# 01_MCU.net
KiCad netlist of a schematic drawn in Altium Designer
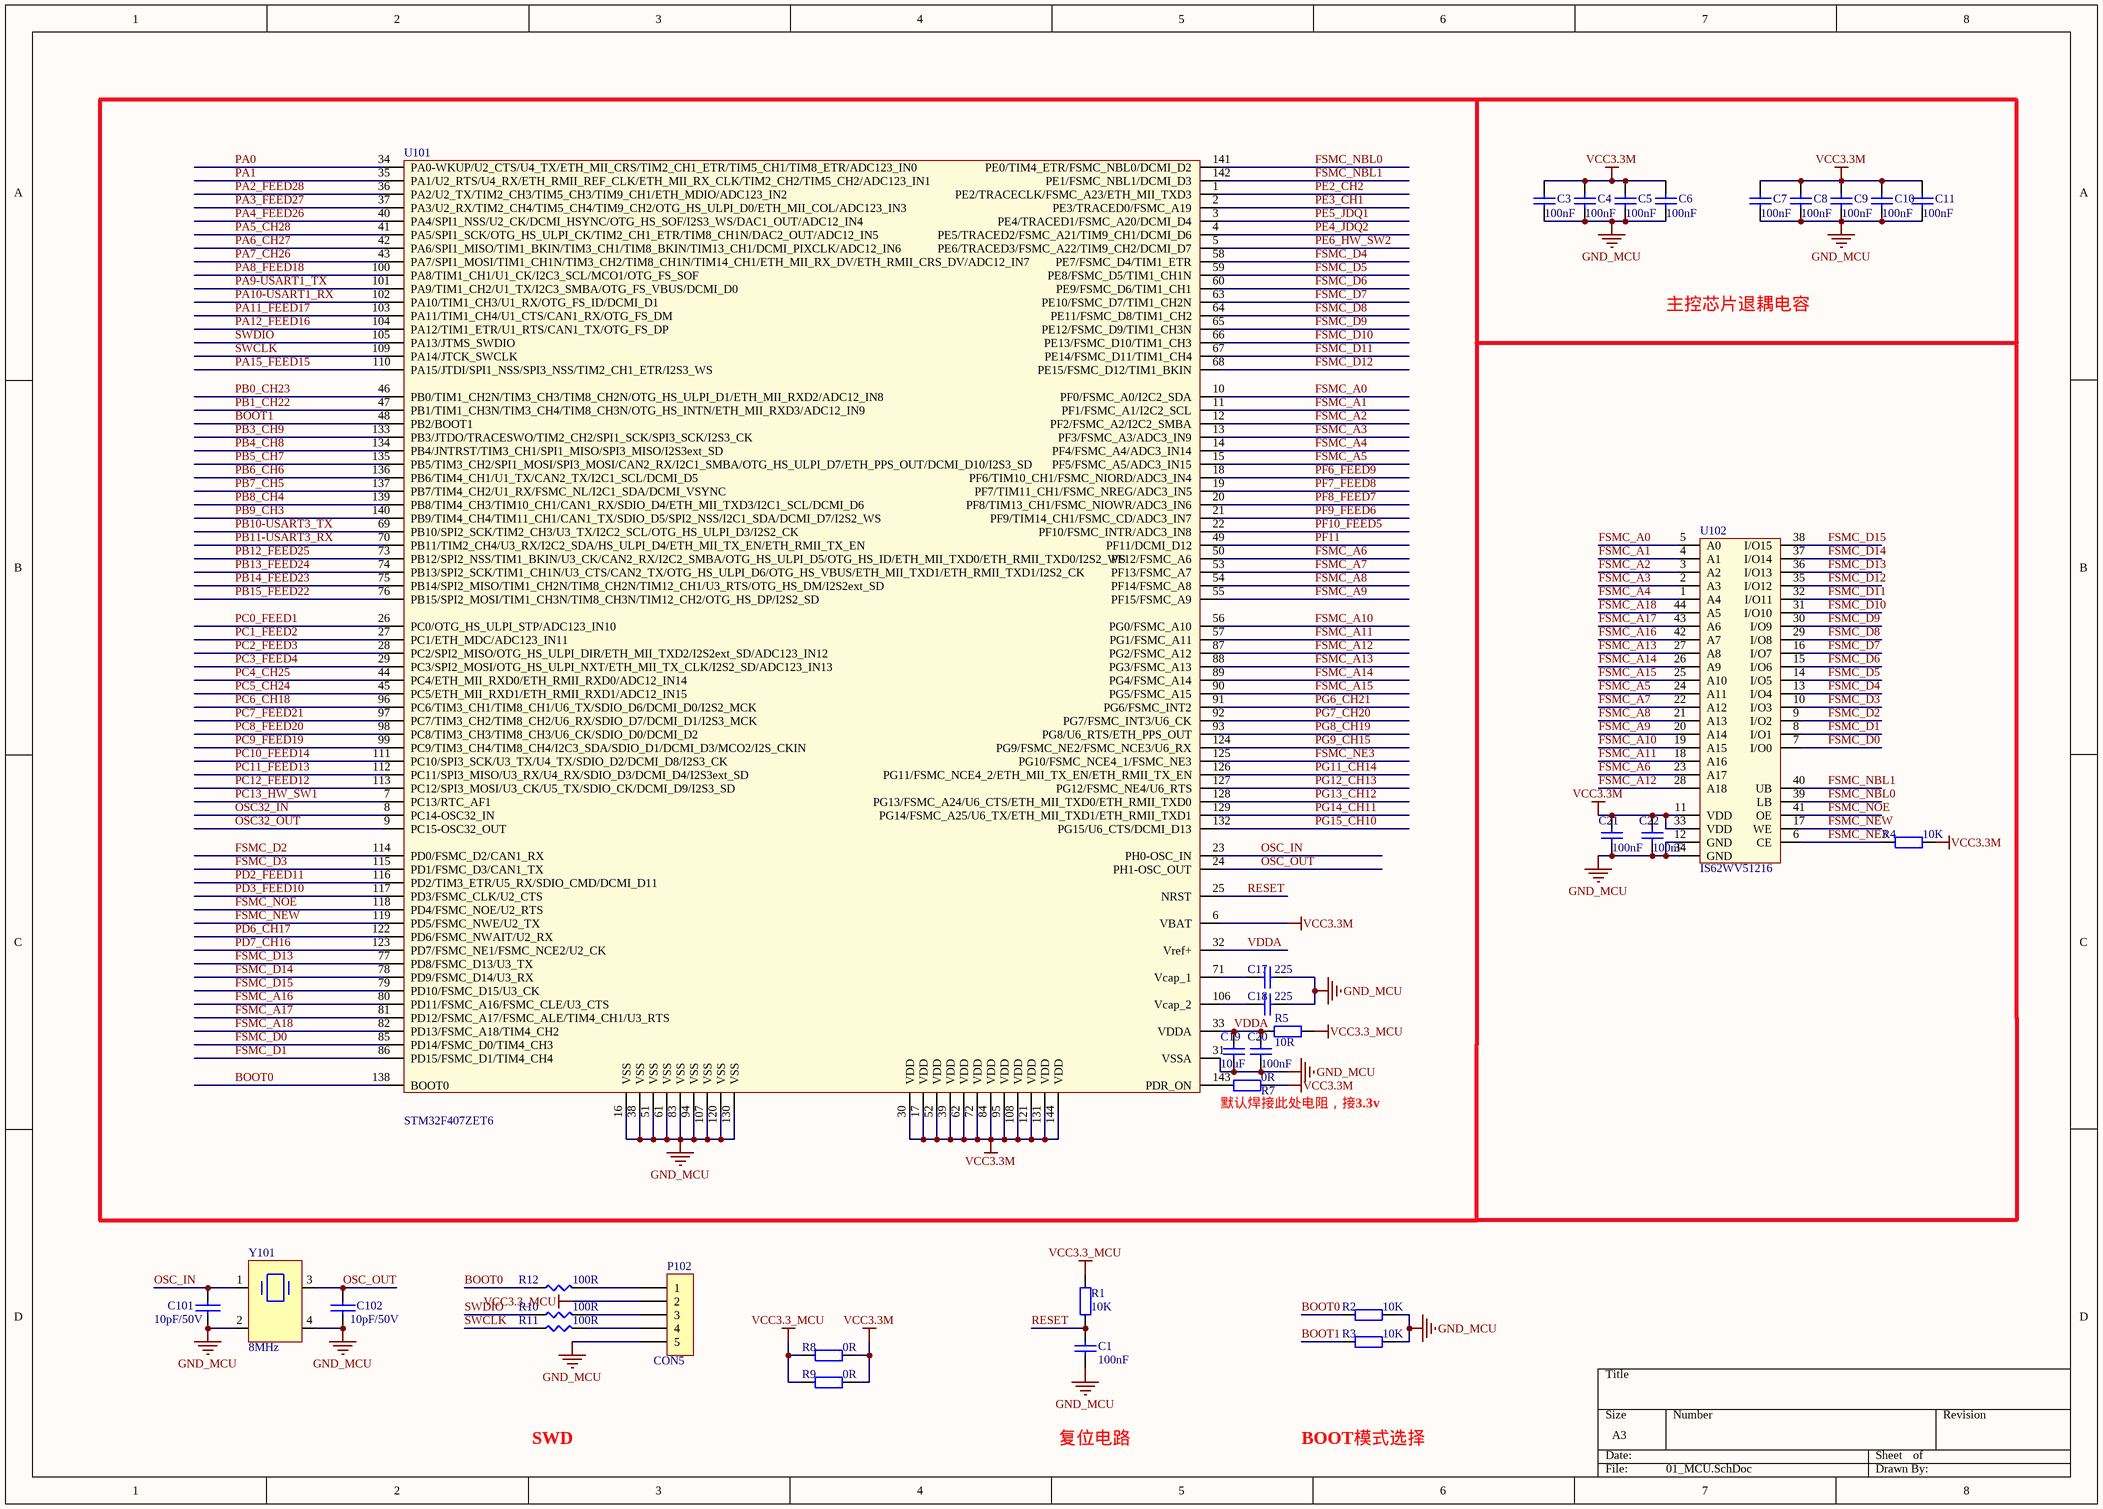
[diagram p0: 01_MCU.SchDoc]

(export (version "E")
  (design (tool "Eeschema 10.0.6"))
  (components
    (comp (ref "C1")
      (value "100nF")
      (footprint "0603C")
      (description "无极性电容")
      (fields (field (name "PUBLISHER") "Altium Limited"))
      (libsource (lib "liu_2016") (part "Cap"))
    )
    (comp (ref "C3")
      (value "100nF")
      (footprint "0603C")
      (description "无极性电容")
      (fields (field (name "PUBLISHER") "Altium Limited"))
      (libsource (lib "liu_2016") (part "Cap"))
    )
    (comp (ref "C4")
      (value "100nF")
      (footprint "0603C")
      (description "无极性电容")
      (fields (field (name "PUBLISHER") "Altium Limited"))
      (libsource (lib "liu_2016") (part "Cap"))
    )
    (comp (ref "C5")
      (value "100nF")
      (footprint "0603C")
      (description "无极性电容")
      (fields (field (name "PUBLISHER") "Altium Limited"))
      (libsource (lib "liu_2016") (part "Cap"))
    )
    (comp (ref "C6")
      (value "100nF")
      (footprint "0603C")
      (description "无极性电容")
      (fields (field (name "PUBLISHER") "Altium Limited"))
      (libsource (lib "liu_2016") (part "Cap"))
    )
    (comp (ref "C7")
      (value "100nF")
      (footprint "0603C")
      (description "无极性电容")
      (fields (field (name "PUBLISHER") "Altium Limited"))
      (libsource (lib "liu_2016") (part "Cap"))
    )
    (comp (ref "C8")
      (value "100nF")
      (footprint "0603C")
      (description "无极性电容")
      (fields (field (name "PUBLISHER") "Altium Limited"))
      (libsource (lib "liu_2016") (part "Cap"))
    )
    (comp (ref "C9")
      (value "100nF")
      (footprint "0603C")
      (description "无极性电容")
      (fields (field (name "PUBLISHER") "Altium Limited"))
      (libsource (lib "liu_2016") (part "Cap"))
    )
    (comp (ref "C10")
      (value "100nF")
      (footprint "0603C")
      (description "无极性电容")
      (fields (field (name "PUBLISHER") "Altium Limited"))
      (libsource (lib "liu_2016") (part "Cap"))
    )
    (comp (ref "C11")
      (value "100nF")
      (footprint "0603C")
      (description "无极性电容")
      (fields (field (name "PUBLISHER") "Altium Limited"))
      (libsource (lib "liu_2016") (part "Cap"))
    )
    (comp (ref "C17")
      (value "225")
      (footprint "0603C")
      (description "无极性电容")
      (fields (field (name "PUBLISHER") "Altium Limited"))
      (libsource (lib "liu_2016") (part "Cap"))
    )
    (comp (ref "C18")
      (value "225")
      (footprint "0603C")
      (description "无极性电容")
      (fields (field (name "PUBLISHER") "Altium Limited"))
      (libsource (lib "liu_2016") (part "Cap"))
    )
    (comp (ref "C19")
      (value "10uF")
      (footprint "0603C")
      (description "无极性电容")
      (fields (field (name "PUBLISHER") "Altium Limited"))
      (libsource (lib "liu_2016") (part "Cap"))
    )
    (comp (ref "C20")
      (value "100nF")
      (footprint "0603C")
      (description "无极性电容")
      (fields (field (name "PUBLISHER") "Altium Limited"))
      (libsource (lib "liu_2016") (part "Cap"))
    )
    (comp (ref "C21")
      (value "100nF")
      (footprint "LC-0603_R")
      (description "无极性电容")
      (fields (field (name "PUBLISHER") "Altium Limited"))
      (libsource (lib "liu_2016") (part "Cap"))
    )
    (comp (ref "C22")
      (value "100nF")
      (footprint "LC-0603_R")
      (description "无极性电容")
      (fields (field (name "PUBLISHER") "Altium Limited"))
      (libsource (lib "liu_2016") (part "Cap"))
    )
    (comp (ref "C101")
      (value "10pF/50V")
      (footprint "0603C")
      (description "Capacitor")
      (libsource (lib "*") (part "CAP"))
    )
    (comp (ref "C102")
      (value "10pF/50V")
      (footprint "0603C")
      (description "Capacitor")
      (libsource (lib "*") (part "CAP"))
    )
    (comp (ref "P102")
      (value "CON5")
      (footprint "SIP5")
      (description "Connector")
      (libsource (lib "*") (part "CON5"))
    )
    (comp (ref "R1")
      (value "10K")
      (footprint "0603R")
      (description "贴片电阻")
      (libsource (lib "Miscellaneous Devices LC") (part "0603 2.7KΩ (2701) 1%"))
    )
    (comp (ref "R2")
      (value "10K")
      (footprint "0603R")
      (description "贴片电阻")
      (libsource (lib "") (part "0603 2.7KΩ (2701) 1%_1"))
    )
    (comp (ref "R3")
      (value "10K")
      (footprint "0603R")
      (description "贴片电阻")
      (libsource (lib "") (part "0603 2.7KΩ (2701) 1%_1"))
    )
    (comp (ref "R4")
      (value "10K")
      (footprint "0603R")
      (description "贴片电阻")
      (libsource (lib "") (part "0603 2.7KΩ (2701) 1%_1"))
    )
    (comp (ref "R5")
      (value "10R")
      (footprint "0603R")
      (description "贴片电阻")
      (libsource (lib "") (part "0603 2.7KΩ (2701) 1%_1"))
    )
    (comp (ref "R7")
      (value "0R")
      (footprint "0603R")
      (description "贴片电阻")
      (libsource (lib "") (part "0603 2.7KΩ (2701) 1%_1"))
    )
    (comp (ref "R8")
      (value "0R")
      (footprint "0805R")
      (description "贴片电阻")
      (libsource (lib "") (part "0603 2.7KΩ (2701) 1%_1"))
    )
    (comp (ref "R9")
      (value "0R")
      (footprint "0805R")
      (description "贴片电阻")
      (libsource (lib "") (part "0603 2.7KΩ (2701) 1%_1"))
    )
    (comp (ref "R10")
      (value "100R")
      (footprint "CD's_LIB_2018:0603R")
      (libsource (lib "CD's_LIB_2018") (part "0603R"))
    )
    (comp (ref "R11")
      (value "100R")
      (footprint "CD's_LIB_2018:0603R")
      (libsource (lib "CD's_LIB_2018") (part "0603R"))
    )
    (comp (ref "R12")
      (value "100R")
      (footprint "CD's_LIB_2018:0603R")
      (libsource (lib "CD's_LIB_2018") (part "0603R"))
    )
    (comp (ref "U101")
      (value "STM32F407ZET6")
      (footprint "TQFP144")
      (libsource (lib "Explorer STM32F407封装库") (part "STM32F407ZET6"))
    )
    (comp (ref "U102")
      (value "IS62WV51216")
      (footprint "TSOP44")
      (libsource (lib "Explorer STM32F407封装库") (part "IS62WV51216"))
    )
    (comp (ref "Y101") (value "8MHz") (footprint "X_TXCWY") (libsource (lib "*") (part "SMD3225")))
  )
  (nets
    (net (code "1") (name "/BOOT0") (class "Default")
      (node (ref "R12") (pin "1") (pinfunction "1_1") (pintype "passive"))
      (node (ref "R2") (pin "1") (pinfunction "1_1") (pintype "passive"))
      (node (ref "U101") (pin "138") (pinfunction "BOOT0_138") (pintype "passive"))
    )
    (net (code "2") (name "/BOOT1") (class "Default")
      (node (ref "R3") (pin "1") (pinfunction "1_1") (pintype "passive"))
      (node (ref "U101") (pin "48") (pinfunction "PB2/BOOT1_48") (pintype "passive"))
    )
    (net (code "3") (name "/FSMC_A0") (class "Default")
      (node (ref "U101") (pin "10") (pinfunction "PF0/FSMC_A0/I2C2_SDA_10") (pintype "passive"))
      (node (ref "U102") (pin "5") (pinfunction "A0_5") (pintype "passive"))
    )
    (net (code "4") (name "/FSMC_A1") (class "Default")
      (node (ref "U101") (pin "11") (pinfunction "PF1/FSMC_A1/I2C2_SCL_11") (pintype "passive"))
      (node (ref "U102") (pin "4") (pinfunction "A1_4") (pintype "passive"))
    )
    (net (code "5") (name "/FSMC_A2") (class "Default")
      (node (ref "U101") (pin "12") (pinfunction "PF2/FSMC_A2/I2C2_SMBA_12") (pintype "passive"))
      (node (ref "U102") (pin "3") (pinfunction "A2_3") (pintype "passive"))
    )
    (net (code "6") (name "/FSMC_A3") (class "Default")
      (node (ref "U101") (pin "13") (pinfunction "PF3/FSMC_A3/ADC3_IN9_13") (pintype "passive"))
      (node (ref "U102") (pin "2") (pinfunction "A3_2") (pintype "passive"))
    )
    (net (code "7") (name "/FSMC_A4") (class "Default")
      (node (ref "U101") (pin "14") (pinfunction "PF4/FSMC_A4/ADC3_IN14_14") (pintype "passive"))
      (node (ref "U102") (pin "1") (pinfunction "A4_1") (pintype "passive"))
    )
    (net (code "8") (name "/FSMC_A5") (class "Default")
      (node (ref "U101") (pin "15") (pinfunction "PF5/FSMC_A5/ADC3_IN15_15") (pintype "passive"))
      (node (ref "U102") (pin "24") (pinfunction "A11_24") (pintype "passive"))
    )
    (net (code "9") (name "/FSMC_A6") (class "Default")
      (node (ref "U101") (pin "50") (pinfunction "PF12/FSMC_A6_50") (pintype "passive"))
      (node (ref "U102") (pin "23") (pinfunction "A17_23") (pintype "passive"))
    )
    (net (code "10") (name "/FSMC_A7") (class "Default")
      (node (ref "U101") (pin "53") (pinfunction "PF13/FSMC_A7_53") (pintype "passive"))
      (node (ref "U102") (pin "22") (pinfunction "A12_22") (pintype "passive"))
    )
    (net (code "11") (name "/FSMC_A8") (class "Default")
      (node (ref "U101") (pin "54") (pinfunction "PF14/FSMC_A8_54") (pintype "passive"))
      (node (ref "U102") (pin "21") (pinfunction "A13_21") (pintype "passive"))
    )
    (net (code "12") (name "/FSMC_A9") (class "Default")
      (node (ref "U101") (pin "55") (pinfunction "PF15/FSMC_A9_55") (pintype "passive"))
      (node (ref "U102") (pin "20") (pinfunction "A14_20") (pintype "passive"))
    )
    (net (code "13") (name "/FSMC_A10") (class "Default")
      (node (ref "U101") (pin "56") (pinfunction "PG0/FSMC_A10_56") (pintype "passive"))
      (node (ref "U102") (pin "19") (pinfunction "A15_19") (pintype "passive"))
    )
    (net (code "14") (name "/FSMC_A11") (class "Default")
      (node (ref "U101") (pin "57") (pinfunction "PG1/FSMC_A11_57") (pintype "passive"))
      (node (ref "U102") (pin "18") (pinfunction "A16_18") (pintype "passive"))
    )
    (net (code "15") (name "/FSMC_A12") (class "Default")
      (node (ref "U101") (pin "87") (pinfunction "PG2/FSMC_A12_87") (pintype "passive"))
      (node (ref "U102") (pin "28") (pinfunction "A18_28") (pintype "passive"))
    )
    (net (code "16") (name "/FSMC_A13") (class "Default")
      (node (ref "U101") (pin "88") (pinfunction "PG3/FSMC_A13_88") (pintype "passive"))
      (node (ref "U102") (pin "27") (pinfunction "A8_27") (pintype "passive"))
    )
    (net (code "17") (name "/FSMC_A14") (class "Default")
      (node (ref "U101") (pin "89") (pinfunction "PG4/FSMC_A14_89") (pintype "passive"))
      (node (ref "U102") (pin "26") (pinfunction "A9_26") (pintype "passive"))
    )
    (net (code "18") (name "/FSMC_A15") (class "Default")
      (node (ref "U101") (pin "90") (pinfunction "PG5/FSMC_A15_90") (pintype "passive"))
      (node (ref "U102") (pin "25") (pinfunction "A10_25") (pintype "passive"))
    )
    (net (code "19") (name "/FSMC_A16") (class "Default")
      (node (ref "U101") (pin "80") (pinfunction "PD11/FSMC_A16/FSMC_CLE/U3_CTS_80") (pintype "passive"))
      (node (ref "U102") (pin "42") (pinfunction "A7_42") (pintype "passive"))
    )
    (net (code "20") (name "/FSMC_A17") (class "Default")
      (node (ref "U101") (pin "81") (pinfunction "PD12/FSMC_A17/FSMC_ALE/TIM4_CH1/U3_RTS_81") (pintype "passive"))
      (node (ref "U102") (pin "43") (pinfunction "A6_43") (pintype "passive"))
    )
    (net (code "21") (name "/FSMC_A18") (class "Default")
      (node (ref "U101") (pin "82") (pinfunction "PD13/FSMC_A18/TIM4_CH2_82") (pintype "passive"))
      (node (ref "U102") (pin "44") (pinfunction "A5_44") (pintype "passive"))
    )
    (net (code "22") (name "/FSMC_D0") (class "Default")
      (node (ref "U101") (pin "85") (pinfunction "PD14/FSMC_D0/TIM4_CH3_85") (pintype "passive"))
      (node (ref "U102") (pin "7") (pinfunction "I/O0_7") (pintype "passive"))
    )
    (net (code "23") (name "/FSMC_D1") (class "Default")
      (node (ref "U101") (pin "86") (pinfunction "PD15/FSMC_D1/TIM4_CH4_86") (pintype "passive"))
      (node (ref "U102") (pin "8") (pinfunction "I/O1_8") (pintype "passive"))
    )
    (net (code "24") (name "/FSMC_D2") (class "Default")
      (node (ref "U101") (pin "114") (pinfunction "PD0/FSMC_D2/CAN1_RX_114") (pintype "passive"))
      (node (ref "U102") (pin "9") (pinfunction "I/O2_9") (pintype "passive"))
    )
    (net (code "25") (name "/FSMC_D3") (class "Default")
      (node (ref "U101") (pin "115") (pinfunction "PD1/FSMC_D3/CAN1_TX_115") (pintype "passive"))
      (node (ref "U102") (pin "10") (pinfunction "I/O3_10") (pintype "passive"))
    )
    (net (code "26") (name "/FSMC_D4") (class "Default")
      (node (ref "U101") (pin "58") (pinfunction "PE7/FSMC_D4/TIM1_ETR_58") (pintype "passive"))
      (node (ref "U102") (pin "13") (pinfunction "I/O4_13") (pintype "passive"))
    )
    (net (code "27") (name "/FSMC_D5") (class "Default")
      (node (ref "U101") (pin "59") (pinfunction "PE8/FSMC_D5/TIM1_CH1N_59") (pintype "passive"))
      (node (ref "U102") (pin "14") (pinfunction "I/O5_14") (pintype "passive"))
    )
    (net (code "28") (name "/FSMC_D6") (class "Default")
      (node (ref "U101") (pin "60") (pinfunction "PE9/FSMC_D6/TIM1_CH1_60") (pintype "passive"))
      (node (ref "U102") (pin "15") (pinfunction "I/O6_15") (pintype "passive"))
    )
    (net (code "29") (name "/FSMC_D7") (class "Default")
      (node (ref "U101") (pin "63") (pinfunction "PE10/FSMC_D7/TIM1_CH2N_63") (pintype "passive"))
      (node (ref "U102") (pin "16") (pinfunction "I/O7_16") (pintype "passive"))
    )
    (net (code "30") (name "/FSMC_D8") (class "Default")
      (node (ref "U101") (pin "64") (pinfunction "PE11/FSMC_D8/TIM1_CH2_64") (pintype "passive"))
      (node (ref "U102") (pin "29") (pinfunction "I/O8_29") (pintype "passive"))
    )
    (net (code "31") (name "/FSMC_D9") (class "Default")
      (node (ref "U101") (pin "65") (pinfunction "PE12/FSMC_D9/TIM1_CH3N_65") (pintype "passive"))
      (node (ref "U102") (pin "30") (pinfunction "I/O9_30") (pintype "passive"))
    )
    (net (code "32") (name "/FSMC_D10") (class "Default")
      (node (ref "U101") (pin "66") (pinfunction "PE13/FSMC_D10/TIM1_CH3_66") (pintype "passive"))
      (node (ref "U102") (pin "31") (pinfunction "I/O10_31") (pintype "passive"))
    )
    (net (code "33") (name "/FSMC_D11") (class "Default")
      (node (ref "U101") (pin "67") (pinfunction "PE14/FSMC_D11/TIM1_CH4_67") (pintype "passive"))
      (node (ref "U102") (pin "32") (pinfunction "I/O11_32") (pintype "passive"))
    )
    (net (code "34") (name "/FSMC_D12") (class "Default")
      (node (ref "U101") (pin "68") (pinfunction "PE15/FSMC_D12/TIM1_BKIN_68") (pintype "passive"))
      (node (ref "U102") (pin "35") (pinfunction "I/O12_35") (pintype "passive"))
    )
    (net (code "35") (name "/FSMC_D13") (class "Default")
      (node (ref "U101") (pin "77") (pinfunction "PD8/FSMC_D13/U3_TX_77") (pintype "passive"))
      (node (ref "U102") (pin "36") (pinfunction "I/O13_36") (pintype "passive"))
    )
    (net (code "36") (name "/FSMC_D14") (class "Default")
      (node (ref "U101") (pin "78") (pinfunction "PD9/FSMC_D14/U3_RX_78") (pintype "passive"))
      (node (ref "U102") (pin "37") (pinfunction "I/O14_37") (pintype "passive"))
    )
    (net (code "37") (name "/FSMC_D15") (class "Default")
      (node (ref "U101") (pin "79") (pinfunction "PD10/FSMC_D15/U3_CK_79") (pintype "passive"))
      (node (ref "U102") (pin "38") (pinfunction "I/O15_38") (pintype "passive"))
    )
    (net (code "38") (name "/FSMC_NBL0") (class "Default")
      (node (ref "U101") (pin "141") (pinfunction "PE0/TIM4_ETR/FSMC_NBL0/DCMI_D2_141") (pintype "passive"))
      (node (ref "U102") (pin "39") (pinfunction "LB_39") (pintype "passive"))
    )
    (net (code "39") (name "/FSMC_NBL1") (class "Default")
      (node (ref "U101") (pin "142") (pinfunction "PE1/FSMC_NBL1/DCMI_D3_142") (pintype "passive"))
      (node (ref "U102") (pin "40") (pinfunction "UB_40") (pintype "passive"))
    )
    (net (code "40") (name "/FSMC_NE3") (class "Default")
      (node (ref "R4") (pin "1") (pinfunction "1_1") (pintype "passive"))
      (node (ref "U101") (pin "125") (pinfunction "PG10/FSMC_NCE4_1/FSMC_NE3_125") (pintype "passive"))
      (node (ref "U102") (pin "6") (pinfunction "CE_6") (pintype "passive"))
    )
    (net (code "41") (name "/FSMC_NEW") (class "Default")
      (node (ref "U101") (pin "119") (pinfunction "PD5/FSMC_NWE/U2_TX_119") (pintype "passive"))
      (node (ref "U102") (pin "17") (pinfunction "WE_17") (pintype "passive"))
    )
    (net (code "42") (name "/FSMC_NOE") (class "Default")
      (node (ref "U101") (pin "118") (pinfunction "PD4/FSMC_NOE/U2_RTS_118") (pintype "passive"))
      (node (ref "U102") (pin "41") (pinfunction "OE_41") (pintype "passive"))
    )
    (net (code "43") (name "/OSC32_IN") (class "Default")
      (node (ref "U101") (pin "8") (pinfunction "PC14-OSC32_IN_8") (pintype "passive"))
    )
    (net (code "44") (name "/OSC32_OUT") (class "Default")
      (node (ref "U101") (pin "9") (pinfunction "PC15-OSC32_OUT_9") (pintype "passive"))
    )
    (net (code "45") (name "/OSC_IN") (class "Default")
      (node (ref "C101") (pin "2") (pinfunction "2_2") (pintype "passive"))
      (node (ref "U101") (pin "23") (pinfunction "PH0-OSC_IN_23") (pintype "passive"))
      (node (ref "Y101") (pin "1") (pinfunction "1_1") (pintype "passive"))
    )
    (net (code "46") (name "/OSC_OUT") (class "Default")
      (node (ref "C102") (pin "2") (pinfunction "2_2") (pintype "passive"))
      (node (ref "U101") (pin "24") (pinfunction "PH1-OSC_OUT_24") (pintype "passive"))
      (node (ref "Y101") (pin "3") (pinfunction "3_3") (pintype "passive"))
    )
    (net (code "47") (name "/PA0") (class "Default")
      (node (ref "U101") (pin "34") (pinfunction "PA0-WKUP/U2_CTS/U4_TX/ETH_MII_CRS/TIM2_CH1_ETR/TIM5_CH1/TIM8_ETR/ADC123_IN0_34") (pintype "passive"))
    )
    (net (code "48") (name "/PA1") (class "Default")
      (node (ref "U101") (pin "35") (pinfunction "PA1/U2_RTS/U4_RX/ETH_RMII_REF_CLK/ETH_MII_RX_CLK/TIM2_CH2/TIM5_CH2/ADC123_IN1_35") (pintype "passive"))
    )
    (net (code "49") (name "/PA2_FEED28") (class "Default")
      (node (ref "U101") (pin "36") (pinfunction "PA2/U2_TX/TIM2_CH3/TIM5_CH3/TIM9_CH1/ETH_MDIO/ADC123_IN2_36") (pintype "passive"))
    )
    (net (code "50") (name "/PA3_FEED27") (class "Default")
      (node (ref "U101") (pin "37") (pinfunction "PA3/U2_RX/TIM2_CH4/TIM5_CH4/TIM9_CH2/OTG_HS_ULPI_D0/ETH_MII_COL/ADC123_IN3_37") (pintype "passive"))
    )
    (net (code "51") (name "/PA4_FEED26") (class "Default")
      (node (ref "U101") (pin "40") (pinfunction "PA4/SPI1_NSS/U2_CK/DCMI_HSYNC/OTG_HS_SOF/I2S3_WS/DAC1_OUT/ADC12_IN4_40") (pintype "passive"))
    )
    (net (code "52") (name "/PA5_CH28") (class "Default")
      (node (ref "U101") (pin "41") (pinfunction "PA5/SPI1_SCK/OTG_HS_ULPI_CK/TIM2_CH1_ETR/TIM8_CH1N/DAC2_OUT/ADC12_IN5_41") (pintype "passive"))
    )
    (net (code "53") (name "/PA6_CH27") (class "Default")
      (node (ref "U101") (pin "42") (pinfunction "PA6/SPI1_MISO/TIM1_BKIN/TIM3_CH1/TIM8_BKIN/TIM13_CH1/DCMI_PIXCLK/ADC12_IN6_42") (pintype "passive"))
    )
    (net (code "54") (name "/PA7_CH26") (class "Default")
      (node (ref "U101") (pin "43") (pinfunction "PA7/SPI1_MOSI/TIM1_CH1N/TIM3_CH2/TIM8_CH1N/TIM14_CH1/ETH_MII_RX_DV/ETH_RMII_CRS_DV/ADC12_IN7_43") (pintype "passive"))
    )
    (net (code "55") (name "/PA8_FEED18") (class "Default")
      (node (ref "U101") (pin "100") (pinfunction "PA8/TIM1_CH1/U1_CK/I2C3_SCL/MCO1/OTG_FS_SOF_100") (pintype "passive"))
    )
    (net (code "56") (name "/PA9-USART1_TX") (class "Default")
      (node (ref "U101") (pin "101") (pinfunction "PA9/TIM1_CH2/U1_TX/I2C3_SMBA/OTG_FS_VBUS/DCMI_D0_101") (pintype "passive"))
    )
    (net (code "57") (name "/PA10-USART1_RX") (class "Default")
      (node (ref "U101") (pin "102") (pinfunction "PA10/TIM1_CH3/U1_RX/OTG_FS_ID/DCMI_D1_102") (pintype "passive"))
    )
    (net (code "58") (name "/PA11_FEED17") (class "Default")
      (node (ref "U101") (pin "103") (pinfunction "PA11/TIM1_CH4/U1_CTS/CAN1_RX/OTG_FS_DM_103") (pintype "passive"))
    )
    (net (code "59") (name "/PA12_FEED16") (class "Default")
      (node (ref "U101") (pin "104") (pinfunction "PA12/TIM1_ETR/U1_RTS/CAN1_TX/OTG_FS_DP_104") (pintype "passive"))
    )
    (net (code "60") (name "/PA15_FEED15") (class "Default")
      (node (ref "U101") (pin "110") (pinfunction "PA15/JTDI/SPI1_NSS/SPI3_NSS/TIM2_CH1_ETR/I2S3_WS_110") (pintype "passive"))
    )
    (net (code "61") (name "/PB0_CH23") (class "Default")
      (node (ref "U101") (pin "46") (pinfunction "PB0/TIM1_CH2N/TIM3_CH3/TIM8_CH2N/OTG_HS_ULPI_D1/ETH_MII_RXD2/ADC12_IN8_46") (pintype "passive"))
    )
    (net (code "62") (name "/PB1_CH22") (class "Default")
      (node (ref "U101") (pin "47") (pinfunction "PB1/TIM1_CH3N/TIM3_CH4/TIM8_CH3N/OTG_HS_INTN/ETH_MII_RXD3/ADC12_IN9_47") (pintype "passive"))
    )
    (net (code "63") (name "/PB3_CH9") (class "Default")
      (node (ref "U101") (pin "133") (pinfunction "PB3/JTDO/TRACESWO/TIM2_CH2/SPI1_SCK/SPI3_SCK/I2S3_CK_133") (pintype "passive"))
    )
    (net (code "64") (name "/PB4_CH8") (class "Default")
      (node (ref "U101") (pin "134") (pinfunction "PB4/JNTRST/TIM3_CH1/SPI1_MISO/SPI3_MISO/I2S3ext_SD_134") (pintype "passive"))
    )
    (net (code "65") (name "/PB5_CH7") (class "Default")
      (node (ref "U101") (pin "135") (pinfunction "PB5/TIM3_CH2/SPI1_MOSI/SPI3_MOSI/CAN2_RX/I2C1_SMBA/OTG_HS_ULPI_D7/ETH_PPS_OUT/DCMI_D10/I2S3_SD_135") (pintype "passive"))
    )
    (net (code "66") (name "/PB6_CH6") (class "Default")
      (node (ref "U101") (pin "136") (pinfunction "PB6/TIM4_CH1/U1_TX/CAN2_TX/I2C1_SCL/DCMI_D5_136") (pintype "passive"))
    )
    (net (code "67") (name "/PB7_CH5") (class "Default")
      (node (ref "U101") (pin "137") (pinfunction "PB7/TIM4_CH2/U1_RX/FSMC_NL/I2C1_SDA/DCMI_VSYNC_137") (pintype "passive"))
    )
    (net (code "68") (name "/PB8_CH4") (class "Default")
      (node (ref "U101") (pin "139") (pinfunction "PB8/TIM4_CH3/TIM10_CH1/CAN1_RX/SDIO_D4/ETH_MII_TXD3/I2C1_SCL/DCMI_D6_139") (pintype "passive"))
    )
    (net (code "69") (name "/PB9_CH3") (class "Default")
      (node (ref "U101") (pin "140") (pinfunction "PB9/TIM4_CH4/TIM11_CH1/CAN1_TX/SDIO_D5/SPI2_NSS/I2C1_SDA/DCMI_D7/I2S2_WS_140") (pintype "passive"))
    )
    (net (code "70") (name "/PB10-USART3_TX") (class "Default")
      (node (ref "U101") (pin "69") (pinfunction "PB10/SPI2_SCK/TIM2_CH3/U3_TX/I2C2_SCL/OTG_HS_ULPI_D3/I2S2_CK_69") (pintype "passive"))
    )
    (net (code "71") (name "/PB11-USART3_RX") (class "Default")
      (node (ref "U101") (pin "70") (pinfunction "PB11/TIM2_CH4/U3_RX/I2C2_SDA/HS_ULPI_D4/ETH_MII_TX_EN/ETH_RMII_TX_EN_70") (pintype "passive"))
    )
    (net (code "72") (name "/PB12_FEED25") (class "Default")
      (node (ref "U101") (pin "73") (pinfunction "PB12/SPI2_NSS/TIM1_BKIN/U3_CK/CAN2_RX/I2C2_SMBA/OTG_HS_ULPI_D5/OTG_HS_ID/ETH_MII_TXD0/ETH_RMII_TXD0/I2S2_WS_73") (pintype "passive"))
    )
    (net (code "73") (name "/PB13_FEED24") (class "Default")
      (node (ref "U101") (pin "74") (pinfunction "PB13/SPI2_SCK/TIM1_CH1N/U3_CTS/CAN2_TX/OTG_HS_ULPI_D6/OTG_HS_VBUS/ETH_MII_TXD1/ETH_RMII_TXD1/I2S2_CK_74") (pintype "passive"))
    )
    (net (code "74") (name "/PB14_FEED23") (class "Default")
      (node (ref "U101") (pin "75") (pinfunction "PB14/SPI2_MISO/TIM1_CH2N/TIM8_CH2N/TIM12_CH1/U3_RTS/OTG_HS_DM/I2S2ext_SD_75") (pintype "passive"))
    )
    (net (code "75") (name "/PB15_FEED22") (class "Default")
      (node (ref "U101") (pin "76") (pinfunction "PB15/SPI2_MOSI/TIM1_CH3N/TIM8_CH3N/TIM12_CH2/OTG_HS_DP/I2S2_SD_76") (pintype "passive"))
    )
    (net (code "76") (name "/PC0_FEED1") (class "Default")
      (node (ref "U101") (pin "26") (pinfunction "PC0/OTG_HS_ULPI_STP/ADC123_IN10_26") (pintype "passive"))
    )
    (net (code "77") (name "/PC1_FEED2") (class "Default")
      (node (ref "U101") (pin "27") (pinfunction "PC1/ETH_MDC/ADC123_IN11_27") (pintype "passive"))
    )
    (net (code "78") (name "/PC2_FEED3") (class "Default")
      (node (ref "U101") (pin "28") (pinfunction "PC2/SPI2_MISO/OTG_HS_ULPI_DIR/ETH_MII_TXD2/I2S2ext_SD/ADC123_IN12_28") (pintype "passive"))
    )
    (net (code "79") (name "/PC3_FEED4") (class "Default")
      (node (ref "U101") (pin "29") (pinfunction "PC3/SPI2_MOSI/OTG_HS_ULPI_NXT/ETH_MII_TX_CLK/I2S2_SD/ADC123_IN13_29") (pintype "passive"))
    )
    (net (code "80") (name "/PC4_CH25") (class "Default")
      (node (ref "U101") (pin "44") (pinfunction "PC4/ETH_MII_RXD0/ETH_RMII_RXD0/ADC12_IN14_44") (pintype "passive"))
    )
    (net (code "81") (name "/PC5_CH24") (class "Default")
      (node (ref "U101") (pin "45") (pinfunction "PC5/ETH_MII_RXD1/ETH_RMII_RXD1/ADC12_IN15_45") (pintype "passive"))
    )
    (net (code "82") (name "/PC6_CH18") (class "Default")
      (node (ref "U101") (pin "96") (pinfunction "PC6/TIM3_CH1/TIM8_CH1/U6_TX/SDIO_D6/DCMI_D0/I2S2_MCK_96") (pintype "passive"))
    )
    (net (code "83") (name "/PC7_FEED21") (class "Default")
      (node (ref "U101") (pin "97") (pinfunction "PC7/TIM3_CH2/TIM8_CH2/U6_RX/SDIO_D7/DCMI_D1/I2S3_MCK_97") (pintype "passive"))
    )
    (net (code "84") (name "/PC8_FEED20") (class "Default")
      (node (ref "U101") (pin "98") (pinfunction "PC8/TIM3_CH3/TIM8_CH3/U6_CK/SDIO_D0/DCMI_D2_98") (pintype "passive"))
    )
    (net (code "85") (name "/PC9_FEED19") (class "Default")
      (node (ref "U101") (pin "99") (pinfunction "PC9/TIM3_CH4/TIM8_CH4/I2C3_SDA/SDIO_D1/DCMI_D3/MCO2/I2S_CKIN_99") (pintype "passive"))
    )
    (net (code "86") (name "/PC10_FEED14") (class "Default")
      (node (ref "U101") (pin "111") (pinfunction "PC10/SPI3_SCK/U3_TX/U4_TX/SDIO_D2/DCMI_D8/I2S3_CK_111") (pintype "passive"))
    )
    (net (code "87") (name "/PC11_FEED13") (class "Default")
      (node (ref "U101") (pin "112") (pinfunction "PC11/SPI3_MISO/U3_RX/U4_RX/SDIO_D3/DCMI_D4/I2S3ext_SD_112") (pintype "passive"))
    )
    (net (code "88") (name "/PC12_FEED12") (class "Default")
      (node (ref "U101") (pin "113") (pinfunction "PC12/SPI3_MOSI/U3_CK/U5_TX/SDIO_CK/DCMI_D9/I2S3_SD_113") (pintype "passive"))
    )
    (net (code "89") (name "/PC13_HW_SW1") (class "Default")
      (node (ref "U101") (pin "7") (pinfunction "PC13/RTC_AF1_7") (pintype "passive"))
    )
    (net (code "90") (name "/PD2_FEED11") (class "Default")
      (node (ref "U101") (pin "116") (pinfunction "PD2/TIM3_ETR/U5_RX/SDIO_CMD/DCMI_D11_116") (pintype "passive"))
    )
    (net (code "91") (name "/PD3_FEED10") (class "Default")
      (node (ref "U101") (pin "117") (pinfunction "PD3/FSMC_CLK/U2_CTS_117") (pintype "passive"))
    )
    (net (code "92") (name "/PD6_CH17") (class "Default")
      (node (ref "U101") (pin "122") (pinfunction "PD6/FSMC_NWAIT/U2_RX_122") (pintype "passive"))
    )
    (net (code "93") (name "/PD7_CH16") (class "Default")
      (node (ref "U101") (pin "123") (pinfunction "PD7/FSMC_NE1/FSMC_NCE2/U2_CK_123") (pintype "passive"))
    )
    (net (code "94") (name "/PE2_CH2") (class "Default")
      (node (ref "U101") (pin "1") (pinfunction "PE2/TRACECLK/FSMC_A23/ETH_MII_TXD3_1") (pintype "passive"))
    )
    (net (code "95") (name "/PE3_CH1") (class "Default")
      (node (ref "U101") (pin "2") (pinfunction "PE3/TRACED0/FSMC_A19_2") (pintype "passive"))
    )
    (net (code "96") (name "/PE4_JDQ2") (class "Default")
      (node (ref "U101") (pin "4") (pinfunction "PE5/TRACED2/FSMC_A21/TIM9_CH1/DCMI_D6_4") (pintype "passive"))
    )
    (net (code "97") (name "/PE5_JDQ1") (class "Default")
      (node (ref "U101") (pin "3") (pinfunction "PE4/TRACED1/FSMC_A20/DCMI_D4_3") (pintype "passive"))
    )
    (net (code "98") (name "/PE6_HW_SW2") (class "Default")
      (node (ref "U101") (pin "5") (pinfunction "PE6/TRACED3/FSMC_A22/TIM9_CH2/DCMI_D7_5") (pintype "passive"))
    )
    (net (code "99") (name "/PF6_FEED9") (class "Default")
      (node (ref "U101") (pin "18") (pinfunction "PF6/TIM10_CH1/FSMC_NIORD/ADC3_IN4_18") (pintype "passive"))
    )
    (net (code "100") (name "/PF7_FEED8") (class "Default")
      (node (ref "U101") (pin "19") (pinfunction "PF7/TIM11_CH1/FSMC_NREG/ADC3_IN5_19") (pintype "passive"))
    )
    (net (code "101") (name "/PF8_FEED7") (class "Default")
      (node (ref "U101") (pin "20") (pinfunction "PF8/TIM13_CH1/FSMC_NIOWR/ADC3_IN6_20") (pintype "passive"))
    )
    (net (code "102") (name "/PF9_FEED6") (class "Default")
      (node (ref "U101") (pin "21") (pinfunction "PF9/TIM14_CH1/FSMC_CD/ADC3_IN7_21") (pintype "passive"))
    )
    (net (code "103") (name "/PF10_FEED5") (class "Default")
      (node (ref "U101") (pin "22") (pinfunction "PF10/FSMC_INTR/ADC3_IN8_22") (pintype "passive"))
    )
    (net (code "104") (name "/PF11") (class "Default")
      (node (ref "U101") (pin "49") (pinfunction "PF11/DCMI_D12_49") (pintype "passive"))
    )
    (net (code "105") (name "/PG6_CH21") (class "Default")
      (node (ref "U101") (pin "91") (pinfunction "PG6/FSMC_INT2_91") (pintype "passive"))
    )
    (net (code "106") (name "/PG7_CH20") (class "Default")
      (node (ref "U101") (pin "92") (pinfunction "PG7/FSMC_INT3/U6_CK_92") (pintype "passive"))
    )
    (net (code "107") (name "/PG8_CH19") (class "Default")
      (node (ref "U101") (pin "93") (pinfunction "PG8/U6_RTS/ETH_PPS_OUT_93") (pintype "passive"))
    )
    (net (code "108") (name "/PG9_CH15") (class "Default")
      (node (ref "U101") (pin "124") (pinfunction "PG9/FSMC_NE2/FSMC_NCE3/U6_RX_124") (pintype "passive"))
    )
    (net (code "109") (name "/PG11_CH14") (class "Default")
      (node (ref "U101") (pin "126") (pinfunction "PG11/FSMC_NCE4_2/ETH_MII_TX_EN/ETH_RMII_TX_EN_126") (pintype "passive"))
    )
    (net (code "110") (name "/PG12_CH13") (class "Default")
      (node (ref "U101") (pin "127") (pinfunction "PG12/FSMC_NE4/U6_RTS_127") (pintype "passive"))
    )
    (net (code "111") (name "/PG13_CH12") (class "Default")
      (node (ref "U101") (pin "128") (pinfunction "PG13/FSMC_A24/U6_CTS/ETH_MII_TXD0/ETH_RMII_TXD0_128") (pintype "passive"))
    )
    (net (code "112") (name "/PG14_CH11") (class "Default")
      (node (ref "U101") (pin "129") (pinfunction "PG14/FSMC_A25/U6_TX/ETH_MII_TXD1/ETH_RMII_TXD1_129") (pintype "passive"))
    )
    (net (code "113") (name "/PG15_CH10") (class "Default")
      (node (ref "U101") (pin "132") (pinfunction "PG15/U6_CTS/DCMI_D13_132") (pintype "passive"))
    )
    (net (code "114") (name "/RESET") (class "Default")
      (node (ref "C1") (pin "2") (pinfunction "2_2") (pintype "passive"))
      (node (ref "R1") (pin "1") (pinfunction "1_1") (pintype "passive"))
      (node (ref "U101") (pin "25") (pinfunction "NRST_25") (pintype "passive"))
    )
    (net (code "115") (name "/SWCLK") (class "Default")
      (node (ref "R11") (pin "1") (pinfunction "1_1") (pintype "passive"))
      (node (ref "U101") (pin "109") (pinfunction "PA14/JTCK_SWCLK_109") (pintype "passive"))
    )
    (net (code "116") (name "/SWDIO") (class "Default")
      (node (ref "R10") (pin "1") (pinfunction "1_1") (pintype "passive"))
      (node (ref "U101") (pin "105") (pinfunction "PA13/JTMS_SWDIO_105") (pintype "passive"))
    )
    (net (code "117") (name "/VDDA") (class "Default")
      (node (ref "C19") (pin "1") (pinfunction "1_1") (pintype "passive"))
      (node (ref "C20") (pin "1") (pinfunction "1_1") (pintype "passive"))
      (node (ref "R5") (pin "1") (pinfunction "1_1") (pintype "passive"))
      (node (ref "U101") (pin "32") (pinfunction "Vref+_32") (pintype "passive"))
      (node (ref "U101") (pin "33") (pinfunction "VDDA_33") (pintype "passive"))
    )
    (net (code "118") (name "GND_MCU") (class "Default")
      (node (ref "C1") (pin "1") (pinfunction "1_1") (pintype "passive"))
      (node (ref "C10") (pin "2") (pinfunction "2_2") (pintype "passive"))
      (node (ref "C101") (pin "1") (pinfunction "1_1") (pintype "passive"))
      (node (ref "C102") (pin "1") (pinfunction "1_1") (pintype "passive"))
      (node (ref "C11") (pin "2") (pinfunction "2_2") (pintype "passive"))
      (node (ref "C17") (pin "1") (pinfunction "1_1") (pintype "passive"))
      (node (ref "C18") (pin "1") (pinfunction "1_1") (pintype "passive"))
      (node (ref "C19") (pin "2") (pinfunction "2_2") (pintype "passive"))
      (node (ref "C20") (pin "2") (pinfunction "2_2") (pintype "passive"))
      (node (ref "C21") (pin "2") (pinfunction "2_2") (pintype "passive"))
      (node (ref "C22") (pin "2") (pinfunction "2_2") (pintype "passive"))
      (node (ref "C3") (pin "2") (pinfunction "2_2") (pintype "passive"))
      (node (ref "C4") (pin "2") (pinfunction "2_2") (pintype "passive"))
      (node (ref "C5") (pin "2") (pinfunction "2_2") (pintype "passive"))
      (node (ref "C6") (pin "2") (pinfunction "2_2") (pintype "passive"))
      (node (ref "C7") (pin "2") (pinfunction "2_2") (pintype "passive"))
      (node (ref "C8") (pin "2") (pinfunction "2_2") (pintype "passive"))
      (node (ref "C9") (pin "2") (pinfunction "2_2") (pintype "passive"))
      (node (ref "P102") (pin "5") (pinfunction "5_5") (pintype "passive"))
      (node (ref "R2") (pin "2") (pinfunction "2_2") (pintype "passive"))
      (node (ref "R3") (pin "2") (pinfunction "2_2") (pintype "passive"))
      (node (ref "U101") (pin "107") (pinfunction "VSS_107") (pintype "passive"))
      (node (ref "U101") (pin "120") (pinfunction "VSS_120") (pintype "passive"))
      (node (ref "U101") (pin "130") (pinfunction "VSS_130") (pintype "passive"))
      (node (ref "U101") (pin "16") (pinfunction "VSS_16") (pintype "passive"))
      (node (ref "U101") (pin "31") (pinfunction "VSSA_31") (pintype "passive"))
      (node (ref "U101") (pin "38") (pinfunction "VSS_38") (pintype "passive"))
      (node (ref "U101") (pin "51") (pinfunction "VSS_51") (pintype "passive"))
      (node (ref "U101") (pin "61") (pinfunction "VSS_61") (pintype "passive"))
      (node (ref "U101") (pin "83") (pinfunction "VSS_83") (pintype "passive"))
      (node (ref "U101") (pin "94") (pinfunction "VSS_94") (pintype "passive"))
      (node (ref "U102") (pin "12") (pinfunction "GND_12") (pintype "passive"))
      (node (ref "U102") (pin "34") (pinfunction "GND_34") (pintype "passive"))
      (node (ref "Y101") (pin "2") (pinfunction "2_2") (pintype "passive"))
      (node (ref "Y101") (pin "4") (pinfunction "4_4") (pintype "passive"))
    )
    (net (code "119") (name "Net-(P102-Pad1)") (class "Default")
      (node (ref "P102") (pin "1") (pinfunction "1_1") (pintype "passive"))
      (node (ref "R12") (pin "2") (pinfunction "2_2") (pintype "passive"))
    )
    (net (code "120") (name "Net-(P102-Pad3)") (class "Default")
      (node (ref "P102") (pin "3") (pinfunction "3_3") (pintype "passive"))
      (node (ref "R10") (pin "2") (pinfunction "2_2") (pintype "passive"))
    )
    (net (code "121") (name "Net-(P102-Pad4)") (class "Default")
      (node (ref "P102") (pin "4") (pinfunction "4_4") (pintype "passive"))
      (node (ref "R11") (pin "2") (pinfunction "2_2") (pintype "passive"))
    )
    (net (code "122") (name "Net-(U101-PDR_ON)") (class "Default")
      (node (ref "R7") (pin "1") (pinfunction "1_1") (pintype "passive"))
      (node (ref "U101") (pin "143") (pinfunction "PDR_ON_143") (pintype "passive"))
    )
    (net (code "123") (name "Net-(U101-Vcap_1)") (class "Default")
      (node (ref "C17") (pin "2") (pinfunction "2_2") (pintype "passive"))
      (node (ref "U101") (pin "71") (pinfunction "Vcap_1_71") (pintype "passive"))
    )
    (net (code "124") (name "Net-(U101-Vcap_2)") (class "Default")
      (node (ref "C18") (pin "2") (pinfunction "2_2") (pintype "passive"))
      (node (ref "U101") (pin "106") (pinfunction "Vcap_2_106") (pintype "passive"))
    )
    (net (code "125") (name "VCC3.3M") (class "Default")
      (node (ref "C10") (pin "1") (pinfunction "1_1") (pintype "passive"))
      (node (ref "C11") (pin "1") (pinfunction "1_1") (pintype "passive"))
      (node (ref "C21") (pin "1") (pinfunction "1_1") (pintype "passive"))
      (node (ref "C22") (pin "1") (pinfunction "1_1") (pintype "passive"))
      (node (ref "C3") (pin "1") (pinfunction "1_1") (pintype "passive"))
      (node (ref "C4") (pin "1") (pinfunction "1_1") (pintype "passive"))
      (node (ref "C5") (pin "1") (pinfunction "1_1") (pintype "passive"))
      (node (ref "C6") (pin "1") (pinfunction "1_1") (pintype "passive"))
      (node (ref "C7") (pin "1") (pinfunction "1_1") (pintype "passive"))
      (node (ref "C8") (pin "1") (pinfunction "1_1") (pintype "passive"))
      (node (ref "C9") (pin "1") (pinfunction "1_1") (pintype "passive"))
      (node (ref "R4") (pin "2") (pinfunction "2_2") (pintype "passive"))
      (node (ref "R7") (pin "2") (pinfunction "2_2") (pintype "passive"))
      (node (ref "R8") (pin "2") (pinfunction "2_2") (pintype "passive"))
      (node (ref "R9") (pin "2") (pinfunction "2_2") (pintype "passive"))
      (node (ref "U101") (pin "108") (pinfunction "VDD_108") (pintype "passive"))
      (node (ref "U101") (pin "121") (pinfunction "VDD_121") (pintype "passive"))
      (node (ref "U101") (pin "131") (pinfunction "VDD_131") (pintype "passive"))
      (node (ref "U101") (pin "144") (pinfunction "VDD_144") (pintype "passive"))
      (node (ref "U101") (pin "17") (pinfunction "VDD_17") (pintype "passive"))
      (node (ref "U101") (pin "30") (pinfunction "VDD_30") (pintype "passive"))
      (node (ref "U101") (pin "39") (pinfunction "VDD_39") (pintype "passive"))
      (node (ref "U101") (pin "52") (pinfunction "VDD_52") (pintype "passive"))
      (node (ref "U101") (pin "6") (pinfunction "VBAT_6") (pintype "passive"))
      (node (ref "U101") (pin "62") (pinfunction "VDD_62") (pintype "passive"))
      (node (ref "U101") (pin "72") (pinfunction "VDD_72") (pintype "passive"))
      (node (ref "U101") (pin "84") (pinfunction "VDD_84") (pintype "passive"))
      (node (ref "U101") (pin "95") (pinfunction "VDD_95") (pintype "passive"))
      (node (ref "U102") (pin "11") (pinfunction "VDD_11") (pintype "passive"))
      (node (ref "U102") (pin "33") (pinfunction "VDD_33") (pintype "passive"))
    )
    (net (code "126") (name "VCC3.3_MCU") (class "Default")
      (node (ref "P102") (pin "2") (pinfunction "2_2") (pintype "passive"))
      (node (ref "R1") (pin "2") (pinfunction "2_2") (pintype "passive"))
      (node (ref "R5") (pin "2") (pinfunction "2_2") (pintype "passive"))
      (node (ref "R8") (pin "1") (pinfunction "1_1") (pintype "passive"))
      (node (ref "R9") (pin "1") (pinfunction "1_1") (pintype "passive"))
    )
  )
)
